# MAIN.net
KiCad netlist of a schematic drawn in Altium Designer
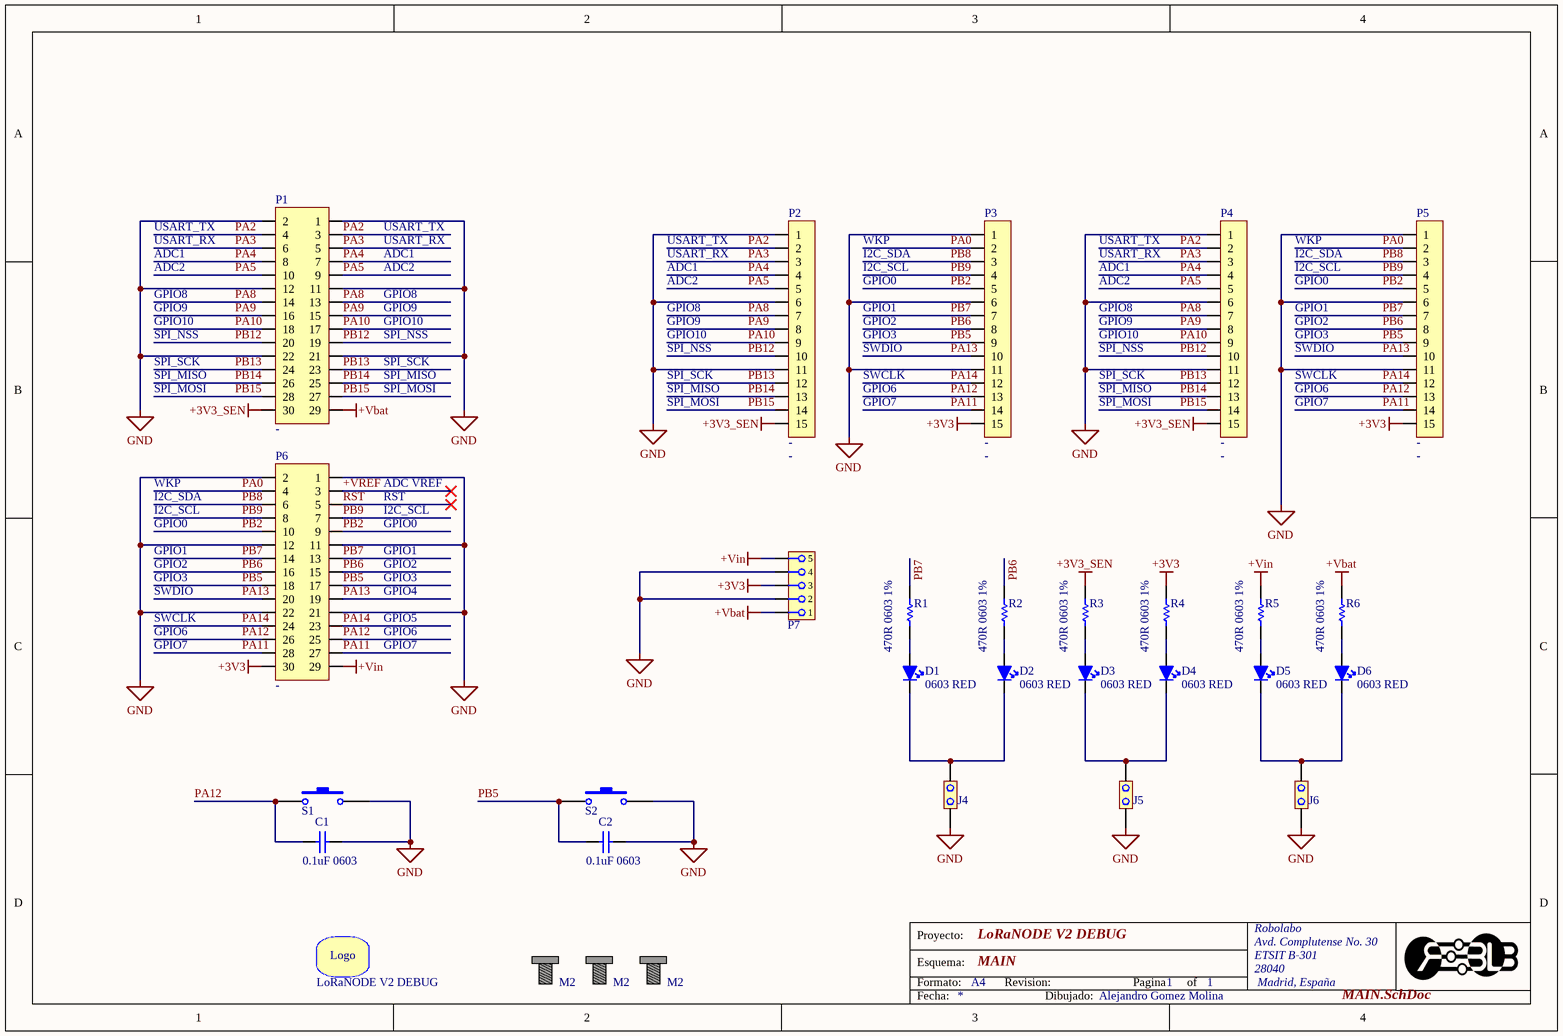
[diagram p0: MAIN.SchDoc]

(export (version "E")
  (design (tool "Eeschema 10.0.6"))
  (components
    (comp (ref "C1")
      (value "0.1uF 0603")
      (footprint "CAP_SMD_0603")
      (description "Cap Ceramic 0.1uF 6.3V X7R 10% Pad SMD 0603 125°C T/R")
      (fields (field (name "TOLERANCE") "10%"))
      (libsource (lib "Ceramic_Capacitor") (part "C0603C104K9RACTU"))
    )
    (comp (ref "C2")
      (value "0.1uF 0603")
      (footprint "CAP_SMD_0603")
      (description "Cap Ceramic 0.1uF 6.3V X7R 10% Pad SMD 0603 125°C T/R")
      (fields (field (name "TOLERANCE") "10%"))
      (libsource (lib "Ceramic_Capacitor") (part "C0603C104K9RACTU"))
    )
    (comp (ref "D1")
      (value "0603 RED")
      (footprint "DIODE_LED_SMD_0603")
      (description "Led, Red, 65MCD, 631NM, SMD, 1608")
      (fields
        (field (name "MANUFACTURER") "Kingbright")
        (field (name "MANUFACTURER PART NUMBER") "KPG1-1608SURC-TT")
      )
      (libsource (lib "LED") (part "KPG1-1608SURC-TT"))
    )
    (comp (ref "D2")
      (value "0603 RED")
      (footprint "DIODE_LED_SMD_0603")
      (description "Led, Red, 65MCD, 631NM, SMD, 1608")
      (fields
        (field (name "MANUFACTURER") "Kingbright")
        (field (name "MANUFACTURER PART NUMBER") "KPG1-1608SURC-TT")
      )
      (libsource (lib "LED") (part "KPG1-1608SURC-TT"))
    )
    (comp (ref "D3")
      (value "0603 RED")
      (footprint "DIODE_LED_SMD_0603")
      (description "Led, Red, 65MCD, 631NM, SMD, 1608")
      (fields
        (field (name "MANUFACTURER") "Kingbright")
        (field (name "MANUFACTURER PART NUMBER") "KPG1-1608SURC-TT")
      )
      (libsource (lib "LED") (part "KPG1-1608SURC-TT"))
    )
    (comp (ref "D4")
      (value "0603 RED")
      (footprint "DIODE_LED_SMD_0603")
      (description "Led, Red, 65MCD, 631NM, SMD, 1608")
      (fields
        (field (name "MANUFACTURER") "Kingbright")
        (field (name "MANUFACTURER PART NUMBER") "KPG1-1608SURC-TT")
      )
      (libsource (lib "LED") (part "KPG1-1608SURC-TT"))
    )
    (comp (ref "D5")
      (value "0603 RED")
      (footprint "DIODE_LED_SMD_0603")
      (description "Led, Red, 65MCD, 631NM, SMD, 1608")
      (fields
        (field (name "MANUFACTURER") "Kingbright")
        (field (name "MANUFACTURER PART NUMBER") "KPG1-1608SURC-TT")
      )
      (libsource (lib "LED") (part "KPG1-1608SURC-TT"))
    )
    (comp (ref "D6")
      (value "0603 RED")
      (footprint "DIODE_LED_SMD_0603")
      (description "Led, Red, 65MCD, 631NM, SMD, 1608")
      (fields
        (field (name "MANUFACTURER") "Kingbright")
        (field (name "MANUFACTURER PART NUMBER") "KPG1-1608SURC-TT")
      )
      (libsource (lib "LED") (part "KPG1-1608SURC-TT"))
    )
    (comp (ref "J4")
      (value "-")
      (footprint "JUMPER_1x2_2.54")
      (libsource (lib "jumper") (part "JUMPER-1x2-2.54"))
    )
    (comp (ref "J5")
      (value "-")
      (footprint "JUMPER_1x2_2.54")
      (libsource (lib "jumper") (part "JUMPER-1x2-2.54"))
    )
    (comp (ref "J6")
      (value "-")
      (footprint "JUMPER_1x2_2.54")
      (libsource (lib "jumper") (part "JUMPER-1x2-2.54"))
    )
    (comp (ref "logo1")
      (value "LoRaNODE V2 DEBUG")
      (footprint "Robolabo10x25")
      (libsource (lib "logo") (part "Robolabo"))
    )
    (comp (ref "P1")
      (value "-")
      (footprint "CONN-2X15-1.27-FEMALE_RECT-SMD")
      (description "CONN-2X15-1.27-MALE-RECT")
      (libsource (lib "pin") (part "CONN-2X15-1.27-FEMALE-RECT"))
    )
    (comp (ref "P2")
      (value "-")
      (footprint "CONN-1X15-2.54-MALE-TH")
      (description "CONN PIN HEADER 15 2.54MM")
      (fields (field (name "SERIGRAFIA") "-"))
      (libsource (lib "pin") (part "CONN-1X15-MALE- RECTO-2.54MM"))
    )
    (comp (ref "P3")
      (value "-")
      (footprint "CONN-1X15-2.54-MALE-TH")
      (description "CONN PIN HEADER 15 2.54MM")
      (fields (field (name "SERIGRAFIA") "-"))
      (libsource (lib "pin") (part "CONN-1X15-MALE- RECTO-2.54MM"))
    )
    (comp (ref "P4")
      (value "-")
      (footprint "CONN-1X15-2.54-MALE-TH-NOPIN")
      (description "CONN PIN HEADER 15 2.54MM")
      (fields (field (name "SERIGRAFIA") "-"))
      (libsource (lib "pin") (part "CONN-1X15-MALE- RECTO-2.54MM"))
    )
    (comp (ref "P5")
      (value "-")
      (footprint "CONN-1X15-2.54-MALE-TH-NOPIN")
      (description "CONN PIN HEADER 15 2.54MM")
      (fields (field (name "SERIGRAFIA") "-"))
      (libsource (lib "pin") (part "CONN-1X15-MALE- RECTO-2.54MM"))
    )
    (comp (ref "P6")
      (value "-")
      (footprint "CONN-2X15-1.27-FEMALE_RECT-SMD")
      (description "CONN-2X15-1.27-MALE-RECT")
      (libsource (lib "pin") (part "CONN-2X15-1.27-FEMALE-RECT"))
    )
    (comp (ref "P7")
      (value "-")
      (footprint "CONN-1X5-2.54-MALE-TH")
      (libsource (lib "pin") (part "CONN-1X5-2.54-MALE-TH"))
    )
    (comp (ref "R1")
      (value "470R 0603 1%")
      (footprint "RES_SMD_0603")
      (description "RES SMD 470 OHM 1% 1/10W 0603")
      (fields (field (name "TOLERANCE") "1%") (field (name "MANUFACTURER") "Vishay"))
      (libsource (lib "Resistor") (part "CRCW0603470RFKEAHP"))
    )
    (comp (ref "R2")
      (value "470R 0603 1%")
      (footprint "RES_SMD_0603")
      (description "RES SMD 470 OHM 1% 1/10W 0603")
      (fields (field (name "TOLERANCE") "1%") (field (name "MANUFACTURER") "Vishay"))
      (libsource (lib "Resistor") (part "CRCW0603470RFKEAHP"))
    )
    (comp (ref "R3")
      (value "470R 0603 1%")
      (footprint "RES_SMD_0603")
      (description "RES SMD 470 OHM 1% 1/10W 0603")
      (fields (field (name "TOLERANCE") "1%") (field (name "MANUFACTURER") "Vishay"))
      (libsource (lib "Resistor") (part "CRCW0603470RFKEAHP"))
    )
    (comp (ref "R4")
      (value "470R 0603 1%")
      (footprint "RES_SMD_0603")
      (description "RES SMD 470 OHM 1% 1/10W 0603")
      (fields (field (name "TOLERANCE") "1%") (field (name "MANUFACTURER") "Vishay"))
      (libsource (lib "Resistor") (part "CRCW0603470RFKEAHP"))
    )
    (comp (ref "R5")
      (value "470R 0603 1%")
      (footprint "RES_SMD_0603")
      (description "RES SMD 470 OHM 1% 1/10W 0603")
      (fields (field (name "TOLERANCE") "1%") (field (name "MANUFACTURER") "Vishay"))
      (libsource (lib "Resistor") (part "CRCW0603470RFKEAHP"))
    )
    (comp (ref "R6")
      (value "470R 0603 1%")
      (footprint "RES_SMD_0603")
      (description "RES SMD 470 OHM 1% 1/10W 0603")
      (fields (field (name "TOLERANCE") "1%") (field (name "MANUFACTURER") "Vishay"))
      (libsource (lib "Resistor") (part "CRCW0603470RFKEAHP"))
    )
    (comp (ref "S1")
      (value "SPST 4.6x2.8mm")
      (footprint "KMR4_CK_SWITCH")
      (fields (field (name "MANUFACTURER") "ITT C&K") (field (name "MANUFACTURER PART NUMBER") "KMR441NGLFS"))
      (libsource (lib "switch") (part "KMR441NGLFS"))
    )
    (comp (ref "S2")
      (value "SPST 4.6x2.8mm")
      (footprint "KMR4_CK_SWITCH")
      (fields (field (name "MANUFACTURER") "ITT C&K") (field (name "MANUFACTURER PART NUMBER") "KMR441NGLFS"))
      (libsource (lib "switch") (part "KMR441NGLFS"))
    )
    (comp (ref "screw1") (value "M2") (footprint "M2") (libsource (lib "screw") (part "screw_M2")))
    (comp (ref "screw2") (value "M2") (footprint "M2_NOPAD") (libsource (lib "screw") (part "screw_M2")))
    (comp (ref "screw3") (value "M2") (footprint "M2_NOPAD") (libsource (lib "screw") (part "screw_M2")))
  )
  (nets
    (net (code "1") (name "+3V3") (class "Default")
      (node (ref "P3") (pin "15") (pinfunction "15_15") (pintype "passive"))
      (node (ref "P5") (pin "15") (pinfunction "15_15") (pintype "passive"))
      (node (ref "P6") (pin "30") (pinfunction "30_30") (pintype "passive"))
      (node (ref "P7") (pin "3") (pinfunction "3_3") (pintype "passive"))
      (node (ref "R4") (pin "2") (pinfunction "2_2") (pintype "passive"))
    )
    (net (code "2") (name "+3V3_SEN") (class "Default")
      (node (ref "P1") (pin "30") (pinfunction "30_30") (pintype "passive"))
      (node (ref "P2") (pin "15") (pinfunction "15_15") (pintype "passive"))
      (node (ref "P4") (pin "15") (pinfunction "15_15") (pintype "passive"))
      (node (ref "R3") (pin "2") (pinfunction "2_2") (pintype "passive"))
    )
    (net (code "3") (name "+Vbat") (class "Default")
      (node (ref "P1") (pin "29") (pinfunction "29_29") (pintype "passive"))
      (node (ref "P7") (pin "1") (pinfunction "1_1") (pintype "passive"))
      (node (ref "R6") (pin "2") (pinfunction "2_2") (pintype "passive"))
    )
    (net (code "4") (name "+Vin") (class "Default")
      (node (ref "P6") (pin "29") (pinfunction "29_29") (pintype "passive"))
      (node (ref "P7") (pin "5") (pinfunction "5_5") (pintype "passive"))
      (node (ref "R5") (pin "2") (pinfunction "2_2") (pintype "passive"))
    )
    (net (code "5") (name "/+VREF") (class "Default")
      (node (ref "P6") (pin "3") (pinfunction "3_3") (pintype "passive+no_connect"))
    )
    (net (code "6") (name "/PA0") (class "Default")
      (node (ref "P3") (pin "2") (pinfunction "2_2") (pintype "passive"))
      (node (ref "P5") (pin "2") (pinfunction "2_2") (pintype "passive"))
      (node (ref "P6") (pin "4") (pinfunction "4_4") (pintype "passive"))
    )
    (net (code "7") (name "/PA2") (class "Default")
      (node (ref "P1") (pin "3") (pinfunction "3_3") (pintype "passive"))
      (node (ref "P1") (pin "4") (pinfunction "4_4") (pintype "passive"))
      (node (ref "P2") (pin "2") (pinfunction "2_2") (pintype "passive"))
      (node (ref "P4") (pin "2") (pinfunction "2_2") (pintype "passive"))
    )
    (net (code "8") (name "/PA3") (class "Default")
      (node (ref "P1") (pin "5") (pinfunction "5_5") (pintype "passive"))
      (node (ref "P1") (pin "6") (pinfunction "6_6") (pintype "passive"))
      (node (ref "P2") (pin "3") (pinfunction "3_3") (pintype "passive"))
      (node (ref "P4") (pin "3") (pinfunction "3_3") (pintype "passive"))
    )
    (net (code "9") (name "/PA4") (class "Default")
      (node (ref "P1") (pin "7") (pinfunction "7_7") (pintype "passive"))
      (node (ref "P1") (pin "8") (pinfunction "8_8") (pintype "passive"))
      (node (ref "P2") (pin "4") (pinfunction "4_4") (pintype "passive"))
      (node (ref "P4") (pin "4") (pinfunction "4_4") (pintype "passive"))
    )
    (net (code "10") (name "/PA5") (class "Default")
      (node (ref "P1") (pin "10") (pinfunction "10_10") (pintype "passive"))
      (node (ref "P1") (pin "9") (pinfunction "9_9") (pintype "passive"))
      (node (ref "P2") (pin "5") (pinfunction "5_5") (pintype "passive"))
      (node (ref "P4") (pin "5") (pinfunction "5_5") (pintype "passive"))
    )
    (net (code "11") (name "/PA8") (class "Default")
      (node (ref "P1") (pin "13") (pinfunction "13_13") (pintype "passive"))
      (node (ref "P1") (pin "14") (pinfunction "14_14") (pintype "passive"))
      (node (ref "P2") (pin "7") (pinfunction "7_7") (pintype "passive"))
      (node (ref "P4") (pin "7") (pinfunction "7_7") (pintype "passive"))
    )
    (net (code "12") (name "/PA9") (class "Default")
      (node (ref "P1") (pin "15") (pinfunction "15_15") (pintype "passive"))
      (node (ref "P1") (pin "16") (pinfunction "16_16") (pintype "passive"))
      (node (ref "P2") (pin "8") (pinfunction "8_8") (pintype "passive"))
      (node (ref "P4") (pin "8") (pinfunction "8_8") (pintype "passive"))
    )
    (net (code "13") (name "/PA10") (class "Default")
      (node (ref "P1") (pin "17") (pinfunction "17_17") (pintype "passive"))
      (node (ref "P1") (pin "18") (pinfunction "18_18") (pintype "passive"))
      (node (ref "P2") (pin "9") (pinfunction "9_9") (pintype "passive"))
      (node (ref "P4") (pin "9") (pinfunction "9_9") (pintype "passive"))
    )
    (net (code "14") (name "/PA11") (class "Default")
      (node (ref "P3") (pin "14") (pinfunction "14_14") (pintype "passive"))
      (node (ref "P5") (pin "14") (pinfunction "14_14") (pintype "passive"))
      (node (ref "P6") (pin "27") (pinfunction "27_27") (pintype "passive"))
      (node (ref "P6") (pin "28") (pinfunction "28_28") (pintype "passive"))
    )
    (net (code "15") (name "/PA12") (class "Default")
      (node (ref "C1") (pin "1") (pinfunction "1_1") (pintype "passive"))
      (node (ref "P3") (pin "13") (pinfunction "13_13") (pintype "passive"))
      (node (ref "P5") (pin "13") (pinfunction "13_13") (pintype "passive"))
      (node (ref "P6") (pin "25") (pinfunction "25_25") (pintype "passive"))
      (node (ref "P6") (pin "26") (pinfunction "26_26") (pintype "passive"))
      (node (ref "S1") (pin "1") (pinfunction "1_1") (pintype "passive"))
    )
    (net (code "16") (name "/PA13") (class "Default")
      (node (ref "P3") (pin "10") (pinfunction "10_10") (pintype "passive"))
      (node (ref "P5") (pin "10") (pinfunction "10_10") (pintype "passive"))
      (node (ref "P6") (pin "19") (pinfunction "19_19") (pintype "passive"))
      (node (ref "P6") (pin "20") (pinfunction "20_20") (pintype "passive"))
    )
    (net (code "17") (name "/PA14") (class "Default")
      (node (ref "P3") (pin "12") (pinfunction "12_12") (pintype "passive"))
      (node (ref "P5") (pin "12") (pinfunction "12_12") (pintype "passive"))
      (node (ref "P6") (pin "23") (pinfunction "23_23") (pintype "passive"))
      (node (ref "P6") (pin "24") (pinfunction "24_24") (pintype "passive"))
    )
    (net (code "18") (name "/PB2") (class "Default")
      (node (ref "P3") (pin "5") (pinfunction "5_5") (pintype "passive"))
      (node (ref "P5") (pin "5") (pinfunction "5_5") (pintype "passive"))
      (node (ref "P6") (pin "10") (pinfunction "10_10") (pintype "passive"))
      (node (ref "P6") (pin "9") (pinfunction "9_9") (pintype "passive"))
    )
    (net (code "19") (name "/PB5") (class "Default")
      (node (ref "C2") (pin "1") (pinfunction "1_1") (pintype "passive"))
      (node (ref "P3") (pin "9") (pinfunction "9_9") (pintype "passive"))
      (node (ref "P5") (pin "9") (pinfunction "9_9") (pintype "passive"))
      (node (ref "P6") (pin "17") (pinfunction "17_17") (pintype "passive"))
      (node (ref "P6") (pin "18") (pinfunction "18_18") (pintype "passive"))
      (node (ref "S2") (pin "1") (pinfunction "1_1") (pintype "passive"))
    )
    (net (code "20") (name "/PB6") (class "Default")
      (node (ref "P3") (pin "8") (pinfunction "8_8") (pintype "passive"))
      (node (ref "P5") (pin "8") (pinfunction "8_8") (pintype "passive"))
      (node (ref "P6") (pin "15") (pinfunction "15_15") (pintype "passive"))
      (node (ref "P6") (pin "16") (pinfunction "16_16") (pintype "passive"))
      (node (ref "R2") (pin "2") (pinfunction "2_2") (pintype "passive"))
    )
    (net (code "21") (name "/PB7") (class "Default")
      (node (ref "P3") (pin "7") (pinfunction "7_7") (pintype "passive"))
      (node (ref "P5") (pin "7") (pinfunction "7_7") (pintype "passive"))
      (node (ref "P6") (pin "13") (pinfunction "13_13") (pintype "passive"))
      (node (ref "P6") (pin "14") (pinfunction "14_14") (pintype "passive"))
      (node (ref "R1") (pin "2") (pinfunction "2_2") (pintype "passive"))
    )
    (net (code "22") (name "/PB8") (class "Default")
      (node (ref "P3") (pin "3") (pinfunction "3_3") (pintype "passive"))
      (node (ref "P5") (pin "3") (pinfunction "3_3") (pintype "passive"))
      (node (ref "P6") (pin "6") (pinfunction "6_6") (pintype "passive"))
    )
    (net (code "23") (name "/PB9") (class "Default")
      (node (ref "P3") (pin "4") (pinfunction "4_4") (pintype "passive"))
      (node (ref "P5") (pin "4") (pinfunction "4_4") (pintype "passive"))
      (node (ref "P6") (pin "7") (pinfunction "7_7") (pintype "passive"))
      (node (ref "P6") (pin "8") (pinfunction "8_8") (pintype "passive"))
    )
    (net (code "24") (name "/PB12") (class "Default")
      (node (ref "P1") (pin "19") (pinfunction "19_19") (pintype "passive"))
      (node (ref "P1") (pin "20") (pinfunction "20_20") (pintype "passive"))
      (node (ref "P2") (pin "10") (pinfunction "10_10") (pintype "passive"))
      (node (ref "P4") (pin "10") (pinfunction "10_10") (pintype "passive"))
    )
    (net (code "25") (name "/PB13") (class "Default")
      (node (ref "P1") (pin "23") (pinfunction "23_23") (pintype "passive"))
      (node (ref "P1") (pin "24") (pinfunction "24_24") (pintype "passive"))
      (node (ref "P2") (pin "12") (pinfunction "12_12") (pintype "passive"))
      (node (ref "P4") (pin "12") (pinfunction "12_12") (pintype "passive"))
    )
    (net (code "26") (name "/PB14") (class "Default")
      (node (ref "P1") (pin "25") (pinfunction "25_25") (pintype "passive"))
      (node (ref "P1") (pin "26") (pinfunction "26_26") (pintype "passive"))
      (node (ref "P2") (pin "13") (pinfunction "13_13") (pintype "passive"))
      (node (ref "P4") (pin "13") (pinfunction "13_13") (pintype "passive"))
    )
    (net (code "27") (name "/PB15") (class "Default")
      (node (ref "P1") (pin "27") (pinfunction "27_27") (pintype "passive"))
      (node (ref "P1") (pin "28") (pinfunction "28_28") (pintype "passive"))
      (node (ref "P2") (pin "14") (pinfunction "14_14") (pintype "passive"))
      (node (ref "P4") (pin "14") (pinfunction "14_14") (pintype "passive"))
    )
    (net (code "28") (name "/RST") (class "Default")
      (node (ref "P6") (pin "5") (pinfunction "5_5") (pintype "passive+no_connect"))
    )
    (net (code "29") (name "GND") (class "Default")
      (node (ref "C1") (pin "2") (pinfunction "2_2") (pintype "passive"))
      (node (ref "C2") (pin "2") (pinfunction "2_2") (pintype "passive"))
      (node (ref "J4") (pin "1") (pinfunction "1_1") (pintype "passive"))
      (node (ref "J5") (pin "1") (pinfunction "1_1") (pintype "passive"))
      (node (ref "J6") (pin "1") (pinfunction "1_1") (pintype "passive"))
      (node (ref "P1") (pin "1") (pinfunction "1_1") (pintype "passive"))
      (node (ref "P1") (pin "11") (pinfunction "11_11") (pintype "passive"))
      (node (ref "P1") (pin "12") (pinfunction "12_12") (pintype "passive"))
      (node (ref "P1") (pin "2") (pinfunction "2_2") (pintype "passive"))
      (node (ref "P1") (pin "21") (pinfunction "21_21") (pintype "passive"))
      (node (ref "P1") (pin "22") (pinfunction "22_22") (pintype "passive"))
      (node (ref "P2") (pin "1") (pinfunction "1_1") (pintype "passive"))
      (node (ref "P2") (pin "11") (pinfunction "11_11") (pintype "passive"))
      (node (ref "P2") (pin "6") (pinfunction "6_6") (pintype "passive"))
      (node (ref "P3") (pin "1") (pinfunction "1_1") (pintype "passive"))
      (node (ref "P3") (pin "11") (pinfunction "11_11") (pintype "passive"))
      (node (ref "P3") (pin "6") (pinfunction "6_6") (pintype "passive"))
      (node (ref "P4") (pin "1") (pinfunction "1_1") (pintype "passive"))
      (node (ref "P4") (pin "11") (pinfunction "11_11") (pintype "passive"))
      (node (ref "P4") (pin "6") (pinfunction "6_6") (pintype "passive"))
      (node (ref "P5") (pin "1") (pinfunction "1_1") (pintype "passive"))
      (node (ref "P5") (pin "11") (pinfunction "11_11") (pintype "passive"))
      (node (ref "P5") (pin "6") (pinfunction "6_6") (pintype "passive"))
      (node (ref "P6") (pin "1") (pinfunction "1_1") (pintype "passive"))
      (node (ref "P6") (pin "11") (pinfunction "11_11") (pintype "passive"))
      (node (ref "P6") (pin "12") (pinfunction "12_12") (pintype "passive"))
      (node (ref "P6") (pin "2") (pinfunction "2_2") (pintype "passive"))
      (node (ref "P6") (pin "21") (pinfunction "21_21") (pintype "passive"))
      (node (ref "P6") (pin "22") (pinfunction "22_22") (pintype "passive"))
      (node (ref "P7") (pin "2") (pinfunction "2_2") (pintype "passive"))
      (node (ref "P7") (pin "4") (pinfunction "4_4") (pintype "passive"))
      (node (ref "S1") (pin "2") (pinfunction "2_2") (pintype "passive"))
      (node (ref "S2") (pin "2") (pinfunction "2_2") (pintype "passive"))
    )
    (net (code "30") (name "Net-(D1-A)") (class "Default")
      (node (ref "D1") (pin "1") (pinfunction "A_1") (pintype "passive"))
      (node (ref "R1") (pin "1") (pinfunction "1_1") (pintype "passive"))
    )
    (net (code "31") (name "Net-(D1-K)") (class "Default")
      (node (ref "D1") (pin "2") (pinfunction "K_2") (pintype "passive"))
      (node (ref "D2") (pin "2") (pinfunction "K_2") (pintype "passive"))
      (node (ref "J4") (pin "2") (pinfunction "2_2") (pintype "passive"))
    )
    (net (code "32") (name "Net-(D2-A)") (class "Default")
      (node (ref "D2") (pin "1") (pinfunction "A_1") (pintype "passive"))
      (node (ref "R2") (pin "1") (pinfunction "1_1") (pintype "passive"))
    )
    (net (code "33") (name "Net-(D3-A)") (class "Default")
      (node (ref "D3") (pin "1") (pinfunction "A_1") (pintype "passive"))
      (node (ref "R3") (pin "1") (pinfunction "1_1") (pintype "passive"))
    )
    (net (code "34") (name "Net-(D3-K)") (class "Default")
      (node (ref "D3") (pin "2") (pinfunction "K_2") (pintype "passive"))
      (node (ref "D4") (pin "2") (pinfunction "K_2") (pintype "passive"))
      (node (ref "J5") (pin "2") (pinfunction "2_2") (pintype "passive"))
    )
    (net (code "35") (name "Net-(D4-A)") (class "Default")
      (node (ref "D4") (pin "1") (pinfunction "A_1") (pintype "passive"))
      (node (ref "R4") (pin "1") (pinfunction "1_1") (pintype "passive"))
    )
    (net (code "36") (name "Net-(D5-A)") (class "Default")
      (node (ref "D5") (pin "1") (pinfunction "A_1") (pintype "passive"))
      (node (ref "R5") (pin "1") (pinfunction "1_1") (pintype "passive"))
    )
    (net (code "37") (name "Net-(D5-K)") (class "Default")
      (node (ref "D5") (pin "2") (pinfunction "K_2") (pintype "passive"))
      (node (ref "D6") (pin "2") (pinfunction "K_2") (pintype "passive"))
      (node (ref "J6") (pin "2") (pinfunction "2_2") (pintype "passive"))
    )
    (net (code "38") (name "Net-(D6-A)") (class "Default")
      (node (ref "D6") (pin "1") (pinfunction "A_1") (pintype "passive"))
      (node (ref "R6") (pin "1") (pinfunction "1_1") (pintype "passive"))
    )
  )
)
